# Prototype.net
KiCad netlist of a schematic drawn in EAGLE
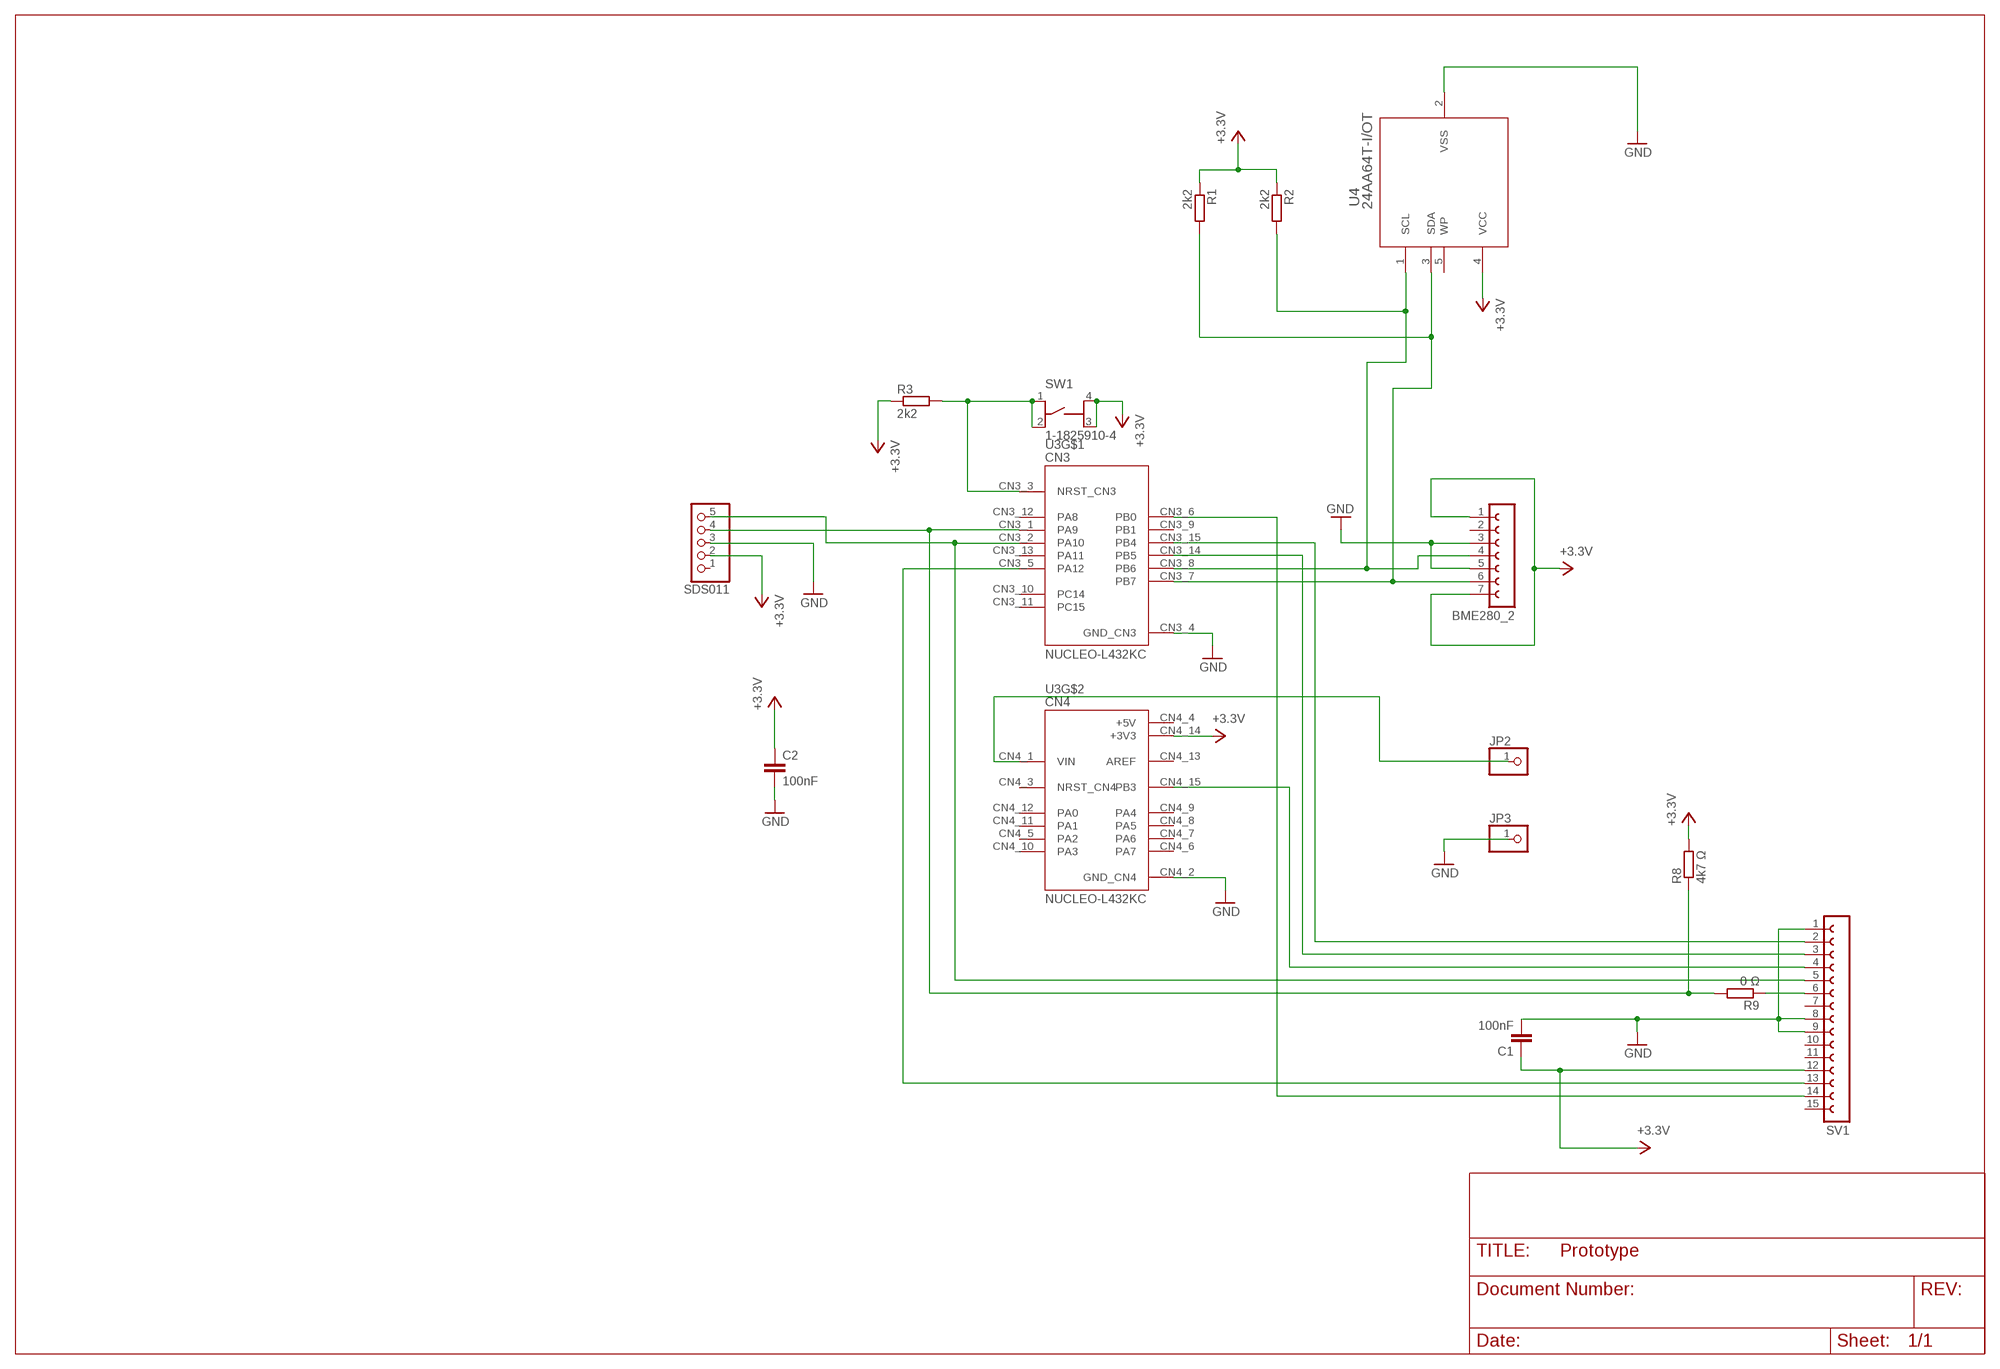
[diagram p0: schematic, sheet 1]

(export (version "E")
  (design (tool "Eeschema 10.0.6"))
  (components
    (comp (ref "BME280_2")
      (value "FE07-1")
      (footprint "eagle-import:FE07")
      (libsource (lib "eagle-import") (part "FE07-1"))
    )
    (comp (ref "C1")
      (value "100nF")
      (footprint "eagle-import:C0603K")
      (libsource (lib "eagle-import") (part "C-EUC0603K"))
    )
    (comp (ref "C2")
      (value "100nF")
      (footprint "eagle-import:C0603K")
      (libsource (lib "eagle-import") (part "C-EUC0603K"))
    )
    (comp (ref "JP2")
      (value "PINHD-1X1")
      (footprint "eagle-import:1X01")
      (libsource (lib "eagle-import") (part "PINHD-1X1"))
    )
    (comp (ref "JP3")
      (value "PINHD-1X1")
      (footprint "eagle-import:1X01")
      (libsource (lib "eagle-import") (part "PINHD-1X1"))
    )
    (comp (ref "R1")
      (value "2k2")
      (footprint "eagle-import:R1206W")
      (libsource (lib "eagle-import") (part "R-EU_R1206W"))
    )
    (comp (ref "R2")
      (value "2k2")
      (footprint "eagle-import:R1206W")
      (libsource (lib "eagle-import") (part "R-EU_R1206W"))
    )
    (comp (ref "R3")
      (value "2k2")
      (footprint "eagle-import:R1206W")
      (libsource (lib "eagle-import") (part "R-EU_R1206W"))
    )
    (comp (ref "R8")
      (value "4k7 Ω")
      (footprint "eagle-import:R1206W")
      (libsource (lib "eagle-import") (part "R-EU_R1206W"))
    )
    (comp (ref "R9")
      (value "0 Ω")
      (footprint "eagle-import:R1206W")
      (libsource (lib "eagle-import") (part "R-EU_R1206W"))
    )
    (comp (ref "SDS011")
      (value "PINHD-1X5")
      (footprint "eagle-import:1X05")
      (libsource (lib "eagle-import") (part "PINHD-1X5"))
    )
    (comp (ref "SV1")
      (value "FE15-1")
      (footprint "eagle-import:FE15")
      (libsource (lib "eagle-import") (part "FE15-1"))
    )
    (comp (ref "SW1")
      (value "1-1825910-4")
      (footprint "eagle-import:TE_1-1825910-4")
      (fields (field (name "MF") "TE Connectivity") (field (name "MP") "118259104"))
      (libsource (lib "eagle-import") (part "1-1825910-4"))
    )
    (comp (ref "U3")
      (value "NUCLEO-L432KC")
      (footprint "eagle-import:MODULE_NUCLEO-L432KC")
      (fields (field (name "MF") "STMicroelectronics"))
      (libsource (lib "eagle-import") (part "NUCLEO-L432KC"))
    )
    (comp (ref "U4")
      (value "24AA64T-I/OT")
      (footprint "eagle-import:SOT-23-5_MC")
      (fields (field (name "COPYRIGHT") "Copyright (C) 2018 Accelerated Designs. All rights reserved"))
      (libsource (lib "eagle-import") (part "24AA64T-I/OT"))
    )
  )
  (nets
    (net (code "1") (name "+3.3V") (class "Default")
      (node (ref "BME280_2") (pin "1") (pinfunction "1_1") (pintype "passive"))
      (node (ref "BME280_2") (pin "7") (pinfunction "7_7") (pintype "passive"))
      (node (ref "C1") (pin "1") (pinfunction "1_1") (pintype "passive"))
      (node (ref "C2") (pin "1") (pinfunction "1_1") (pintype "passive"))
      (node (ref "R1") (pin "1") (pinfunction "1_1") (pintype "passive"))
      (node (ref "R2") (pin "1") (pinfunction "1_1") (pintype "passive"))
      (node (ref "R3") (pin "1") (pinfunction "1_1") (pintype "passive"))
      (node (ref "R8") (pin "2") (pinfunction "2_2") (pintype "passive"))
      (node (ref "SDS011") (pin "2") (pinfunction "2_2") (pintype "passive"))
      (node (ref "SV1") (pin "12") (pinfunction "12_12") (pintype "passive"))
      (node (ref "SW1") (pin "3") (pinfunction "3_3") (pintype "passive"))
      (node (ref "SW1") (pin "4") (pinfunction "4_4") (pintype "passive"))
      (node (ref "U3") (pin "CN4_14") (pinfunction "+3V3_CN4_14") (pintype "power_in"))
      (node (ref "U4") (pin "4") (pinfunction "VCC_4") (pintype "power_in"))
    )
    (net (code "2") (name "/+5V") (class "Default")
      (node (ref "U3") (pin "CN4_4") (pinfunction "+5V_CN4_4") (pintype "power_in"))
    )
    (net (code "3") (name "GND") (class "Default")
      (node (ref "BME280_2") (pin "3") (pinfunction "3_3") (pintype "passive"))
      (node (ref "BME280_2") (pin "5") (pinfunction "5_5") (pintype "passive"))
      (node (ref "C1") (pin "2") (pinfunction "2_2") (pintype "passive"))
      (node (ref "C2") (pin "2") (pinfunction "2_2") (pintype "passive"))
      (node (ref "JP3") (pin "1") (pinfunction "1_1") (pintype "passive"))
      (node (ref "SDS011") (pin "3") (pinfunction "3_3") (pintype "passive"))
      (node (ref "SV1") (pin "1") (pinfunction "1_1") (pintype "passive"))
      (node (ref "SV1") (pin "8") (pinfunction "8_8") (pintype "passive"))
      (node (ref "SV1") (pin "9") (pinfunction "9_9") (pintype "passive"))
      (node (ref "U3") (pin "CN3_4") (pinfunction "GND_CN3_CN3_4") (pintype "power_in"))
      (node (ref "U3") (pin "CN4_2") (pinfunction "GND_CN4_CN4_2") (pintype "power_in"))
      (node (ref "U4") (pin "2") (pinfunction "VSS_2") (pintype "power_in"))
    )
    (net (code "4") (name "Net-(R9-Pad1)") (class "Default")
      (node (ref "R9") (pin "1") (pinfunction "1_1") (pintype "passive"))
      (node (ref "SV1") (pin "6") (pinfunction "6_6") (pintype "passive"))
    )
    (net (code "5") (name "Net-(U3A-NRST_CN3)") (class "Default")
      (node (ref "R3") (pin "2") (pinfunction "2_2") (pintype "passive"))
      (node (ref "SW1") (pin "1") (pinfunction "1_1") (pintype "passive"))
      (node (ref "SW1") (pin "2") (pinfunction "2_2") (pintype "passive"))
      (node (ref "U3") (pin "CN3_3") (pinfunction "NRST_CN3_CN3_3") (pintype "bidirectional"))
    )
    (net (code "6") (name "Net-(U3A-PA9)") (class "Default")
      (node (ref "R8") (pin "1") (pinfunction "1_1") (pintype "passive"))
      (node (ref "R9") (pin "2") (pinfunction "2_2") (pintype "passive"))
      (node (ref "SDS011") (pin "4") (pinfunction "4_4") (pintype "passive"))
      (node (ref "U3") (pin "CN3_1") (pinfunction "PA9_CN3_1") (pintype "bidirectional"))
    )
    (net (code "7") (name "Net-(U3A-PA10)") (class "Default")
      (node (ref "SDS011") (pin "5") (pinfunction "5_5") (pintype "passive"))
      (node (ref "SV1") (pin "5") (pinfunction "5_5") (pintype "passive"))
      (node (ref "U3") (pin "CN3_2") (pinfunction "PA10_CN3_2") (pintype "bidirectional"))
    )
    (net (code "8") (name "Net-(U3A-PA12)") (class "Default")
      (node (ref "SV1") (pin "13") (pinfunction "13_13") (pintype "passive"))
      (node (ref "U3") (pin "CN3_5") (pinfunction "PA12_CN3_5") (pintype "bidirectional"))
    )
    (net (code "9") (name "Net-(U3A-PB0)") (class "Default")
      (node (ref "SV1") (pin "14") (pinfunction "14_14") (pintype "passive"))
      (node (ref "U3") (pin "CN3_6") (pinfunction "PB0_CN3_6") (pintype "bidirectional"))
    )
    (net (code "10") (name "Net-(U3A-PB4)") (class "Default")
      (node (ref "SV1") (pin "2") (pinfunction "2_2") (pintype "passive"))
      (node (ref "U3") (pin "CN3_15") (pinfunction "PB4_CN3_15") (pintype "bidirectional"))
    )
    (net (code "11") (name "Net-(U3A-PB5)") (class "Default")
      (node (ref "SV1") (pin "3") (pinfunction "3_3") (pintype "passive"))
      (node (ref "U3") (pin "CN3_14") (pinfunction "PB5_CN3_14") (pintype "bidirectional"))
    )
    (net (code "12") (name "Net-(U3A-PB6)") (class "Default")
      (node (ref "BME280_2") (pin "4") (pinfunction "4_4") (pintype "passive"))
      (node (ref "R2") (pin "2") (pinfunction "2_2") (pintype "passive"))
      (node (ref "U3") (pin "CN3_8") (pinfunction "PB6_CN3_8") (pintype "bidirectional"))
      (node (ref "U4") (pin "1") (pinfunction "SCL_1") (pintype "input"))
    )
    (net (code "13") (name "Net-(U3A-PB7)") (class "Default")
      (node (ref "BME280_2") (pin "6") (pinfunction "6_6") (pintype "passive"))
      (node (ref "R1") (pin "2") (pinfunction "2_2") (pintype "passive"))
      (node (ref "U3") (pin "CN3_7") (pinfunction "PB7_CN3_7") (pintype "bidirectional"))
      (node (ref "U4") (pin "3") (pinfunction "SDA_3") (pintype "bidirectional"))
    )
    (net (code "14") (name "Net-(U3B-PB3)") (class "Default")
      (node (ref "SV1") (pin "4") (pinfunction "4_4") (pintype "passive"))
      (node (ref "U3") (pin "CN4_15") (pinfunction "PB3_CN4_15") (pintype "bidirectional"))
    )
    (net (code "15") (name "Net-(U3B-VIN)") (class "Default")
      (node (ref "JP2") (pin "1") (pinfunction "1_1") (pintype "passive"))
      (node (ref "U3") (pin "CN4_1") (pinfunction "VIN_CN4_1") (pintype "input"))
    )
    (net (code "16") (name "unconnected-(BME280_2-Pad2)") (class "Default")
      (node (ref "BME280_2") (pin "2") (pinfunction "2_2") (pintype "passive"))
    )
    (net (code "17") (name "unconnected-(SDS011-Pad1)") (class "Default")
      (node (ref "SDS011") (pin "1") (pinfunction "1_1") (pintype "passive"))
    )
    (net (code "18") (name "unconnected-(SV1-Pad7)") (class "Default")
      (node (ref "SV1") (pin "7") (pinfunction "7_7") (pintype "passive"))
    )
    (net (code "19") (name "unconnected-(SV1-Pad10)") (class "Default")
      (node (ref "SV1") (pin "10") (pinfunction "10_10") (pintype "passive"))
    )
    (net (code "20") (name "unconnected-(SV1-Pad11)") (class "Default")
      (node (ref "SV1") (pin "11") (pinfunction "11_11") (pintype "passive"))
    )
    (net (code "21") (name "unconnected-(SV1-Pad15)") (class "Default")
      (node (ref "SV1") (pin "15") (pinfunction "15_15") (pintype "passive"))
    )
    (net (code "22") (name "unconnected-(U3A-PA8-PadCN3_12)") (class "Default")
      (node (ref "U3") (pin "CN3_12") (pinfunction "PA8_CN3_12") (pintype "bidirectional"))
    )
    (net (code "23") (name "unconnected-(U3A-PA11-PadCN3_13)") (class "Default")
      (node (ref "U3") (pin "CN3_13") (pinfunction "PA11_CN3_13") (pintype "bidirectional"))
    )
    (net (code "24") (name "unconnected-(U3A-PB1-PadCN3_9)") (class "Default")
      (node (ref "U3") (pin "CN3_9") (pinfunction "PB1_CN3_9") (pintype "bidirectional"))
    )
    (net (code "25") (name "unconnected-(U3A-PC14-PadCN3_10)") (class "Default")
      (node (ref "U3") (pin "CN3_10") (pinfunction "PC14_CN3_10") (pintype "bidirectional"))
    )
    (net (code "26") (name "unconnected-(U3A-PC15-PadCN3_11)") (class "Default")
      (node (ref "U3") (pin "CN3_11") (pinfunction "PC15_CN3_11") (pintype "bidirectional"))
    )
    (net (code "27") (name "unconnected-(U3B-AREF-PadCN4_13)") (class "Default")
      (node (ref "U3") (pin "CN4_13") (pinfunction "AREF_CN4_13") (pintype "bidirectional"))
    )
    (net (code "28") (name "unconnected-(U3B-NRST_CN4-PadCN4_3)") (class "Default")
      (node (ref "U3") (pin "CN4_3") (pinfunction "NRST_CN4_CN4_3") (pintype "bidirectional"))
    )
    (net (code "29") (name "unconnected-(U3B-PA0-PadCN4_12)") (class "Default")
      (node (ref "U3") (pin "CN4_12") (pinfunction "PA0_CN4_12") (pintype "bidirectional"))
    )
    (net (code "30") (name "unconnected-(U3B-PA1-PadCN4_11)") (class "Default")
      (node (ref "U3") (pin "CN4_11") (pinfunction "PA1_CN4_11") (pintype "bidirectional"))
    )
    (net (code "31") (name "unconnected-(U3B-PA2-PadCN4_5)") (class "Default")
      (node (ref "U3") (pin "CN4_5") (pinfunction "PA2_CN4_5") (pintype "bidirectional"))
    )
    (net (code "32") (name "unconnected-(U3B-PA3-PadCN4_10)") (class "Default")
      (node (ref "U3") (pin "CN4_10") (pinfunction "PA3_CN4_10") (pintype "bidirectional"))
    )
    (net (code "33") (name "unconnected-(U3B-PA4-PadCN4_9)") (class "Default")
      (node (ref "U3") (pin "CN4_9") (pinfunction "PA4_CN4_9") (pintype "bidirectional"))
    )
    (net (code "34") (name "unconnected-(U3B-PA5-PadCN4_8)") (class "Default")
      (node (ref "U3") (pin "CN4_8") (pinfunction "PA5_CN4_8") (pintype "bidirectional"))
    )
    (net (code "35") (name "unconnected-(U3B-PA6-PadCN4_7)") (class "Default")
      (node (ref "U3") (pin "CN4_7") (pinfunction "PA6_CN4_7") (pintype "bidirectional"))
    )
    (net (code "36") (name "unconnected-(U3B-PA7-PadCN4_6)") (class "Default")
      (node (ref "U3") (pin "CN4_6") (pinfunction "PA7_CN4_6") (pintype "bidirectional"))
    )
    (net (code "37") (name "unconnected-(U4-WP-Pad5)") (class "Default")
      (node (ref "U4") (pin "5") (pinfunction "WP_5") (pintype "passive"))
    )
  )
)
